# MicroController_AHRS.net
KiCad netlist of a schematic drawn in Altium Designer
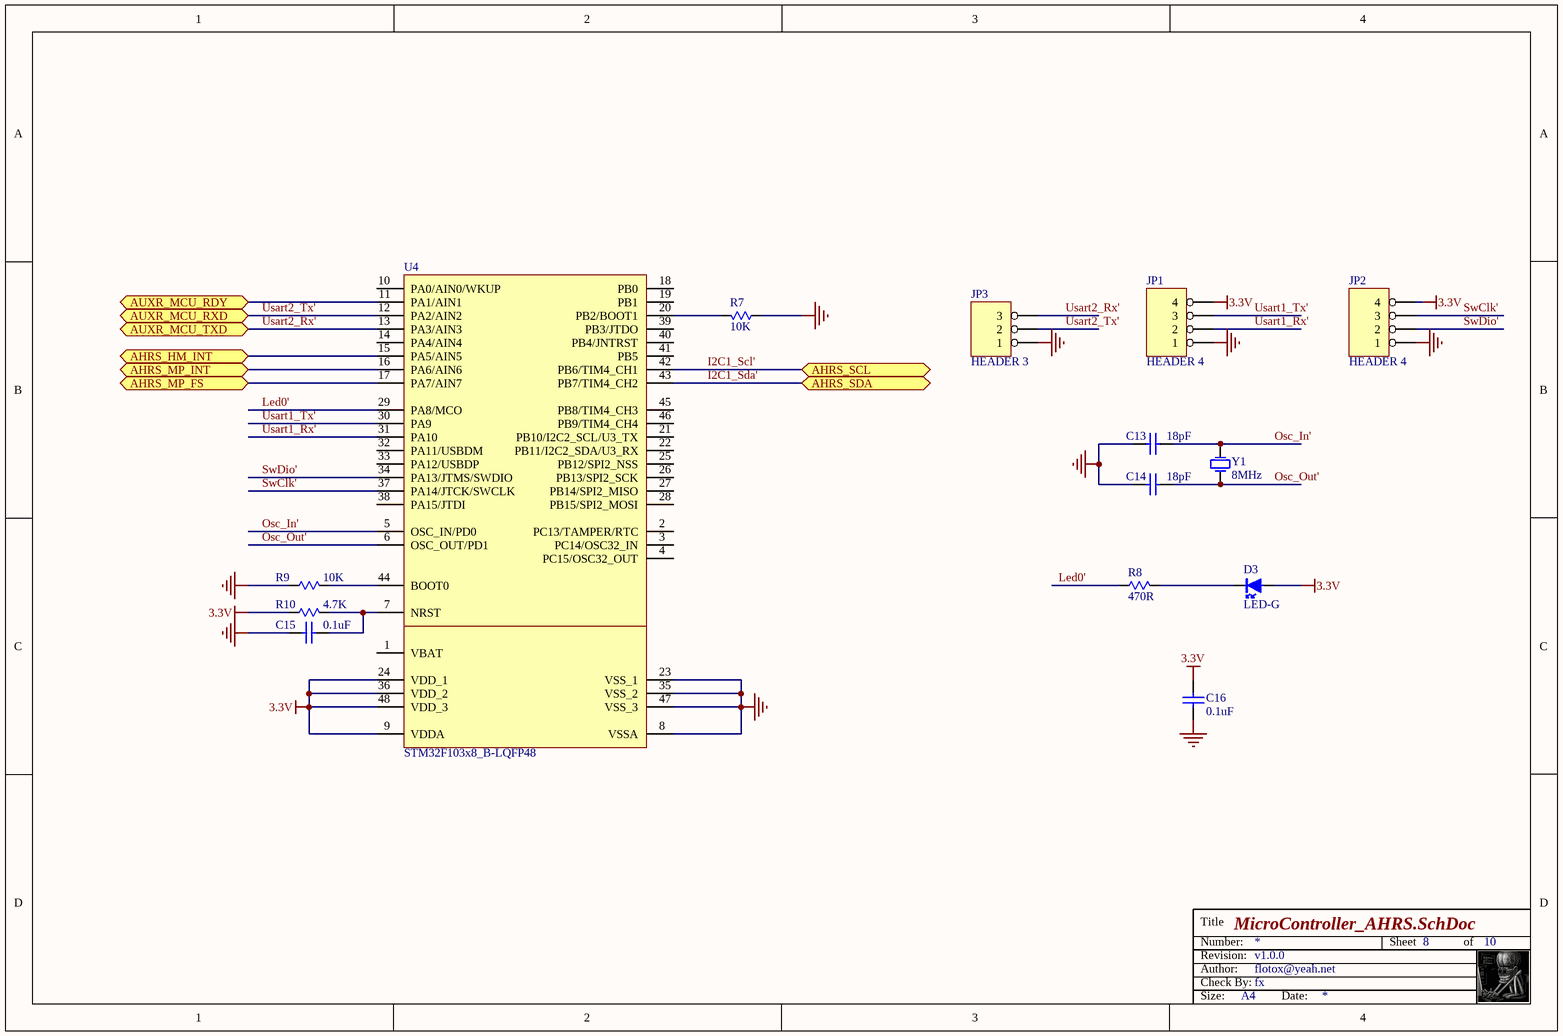
[diagram p0: MicroController_AHRS.SchDoc]

(export (version "E")
  (design (tool "Eeschema 10.0.6"))
  (components
    (comp (ref "C13")
      (value "18pF")
      (footprint "C0603-S")
      (description "Capacitor")
      (libsource (lib "Passive Components Class") (part "CAP"))
    )
    (comp (ref "C14")
      (value "18pF")
      (footprint "C0603-S")
      (description "Capacitor")
      (libsource (lib "Passive Components Class") (part "CAP"))
    )
    (comp (ref "C15")
      (value "0.1uF")
      (footprint "C0603-S")
      (description "Capacitor")
      (libsource (lib "Passive Components Class") (part "CAP"))
    )
    (comp (ref "C16")
      (value "0.1uF")
      (footprint "C0603-S")
      (description "Capacitor")
      (libsource (lib "Passive Components Class") (part "CAP"))
    )
    (comp (ref "D3")
      (value "LED-G")
      (footprint "LED0603")
      (description "Light Emitting Diode")
      (libsource (lib "Passive Components Class") (part "LED"))
    )
    (comp (ref "JP1")
      (value "HEADER 4")
      (footprint "SPOX-4P")
      (libsource (lib "Connector Class") (part "HEADER 4"))
    )
    (comp (ref "JP2")
      (value "HEADER 4")
      (footprint "HDR1X4")
      (libsource (lib "Connector Class") (part "HEADER 4"))
    )
    (comp (ref "JP3")
      (value "HEADER 3")
      (footprint "HDR1X3")
      (libsource (lib "Connector Class") (part "HEADER 3"))
    )
    (comp (ref "R7")
      (value "10K")
      (footprint "R0603-S")
      (description "Resistor")
      (libsource (lib "Passive Components Class") (part "RES"))
    )
    (comp (ref "R8")
      (value "470R")
      (footprint "R0603-S")
      (description "Resistor")
      (libsource (lib "Passive Components Class") (part "RES"))
    )
    (comp (ref "R9")
      (value "10K")
      (footprint "R0603-S")
      (description "Resistor")
      (libsource (lib "Passive Components Class") (part "RES"))
    )
    (comp (ref "R10")
      (value "4.7K")
      (footprint "R0603-S")
      (description "Resistor")
      (libsource (lib "Passive Components Class") (part "RES"))
    )
    (comp (ref "U4")
      (value "STM32F103x8_B-LQFP48")
      (footprint "LQFP7x7-48")
      (libsource (lib "Microcontrollers Class") (part "STM32F103x8_B-LQFP48"))
    )
    (comp (ref "Y1")
      (value "8MHz")
      (footprint "XTAL-49SMD")
      (description "Crystals")
      (libsource (lib "Passive Components Class") (part "XTAL-CRYSTALS"))
    )
  )
  (nets
    (net (code "1") (name "/AHRS_HM_INT") (class "Default")
      (node (ref "U4") (pin "15") (pinfunction "PA5/AIN5_15") (pintype "passive"))
    )
    (net (code "2") (name "/AHRS_MP_FS") (class "Default")
      (node (ref "U4") (pin "17") (pinfunction "PA7/AIN7_17") (pintype "passive"))
    )
    (net (code "3") (name "/AHRS_MP_INT") (class "Default")
      (node (ref "U4") (pin "16") (pinfunction "PA6/AIN6_16") (pintype "passive"))
    )
    (net (code "4") (name "/AUXR_MCU_RDY") (class "Default")
      (node (ref "U4") (pin "11") (pinfunction "PA1/AIN1_11") (pintype "passive"))
    )
    (net (code "5") (name "/I2C1_Scl'") (class "Default")
      (node (ref "U4") (pin "42") (pinfunction "PB6/TIM4_CH1_42") (pintype "passive"))
    )
    (net (code "6") (name "/I2C1_Sda'") (class "Default")
      (node (ref "U4") (pin "43") (pinfunction "PB7/TIM4_CH2_43") (pintype "passive"))
    )
    (net (code "7") (name "/Led0'") (class "Default")
      (node (ref "R8") (pin "2") (pinfunction "2_2") (pintype "passive"))
      (node (ref "U4") (pin "29") (pinfunction "PA8/MCO_29") (pintype "passive"))
    )
    (net (code "8") (name "/Osc_In'") (class "Default")
      (node (ref "C13") (pin "1") (pinfunction "1_1") (pintype "passive"))
      (node (ref "U4") (pin "5") (pinfunction "OSC_IN/PD0_5") (pintype "passive"))
      (node (ref "Y1") (pin "1") (pinfunction "OSC1_1") (pintype "passive"))
    )
    (net (code "9") (name "/Osc_Out'") (class "Default")
      (node (ref "C14") (pin "1") (pinfunction "1_1") (pintype "passive"))
      (node (ref "U4") (pin "6") (pinfunction "OSC_OUT/PD1_6") (pintype "passive"))
      (node (ref "Y1") (pin "2") (pinfunction "OSC2_2") (pintype "passive"))
    )
    (net (code "10") (name "/SwClk'") (class "Default")
      (node (ref "JP2") (pin "3") (pinfunction "3_3") (pintype "passive"))
      (node (ref "U4") (pin "37") (pinfunction "PA14/JTCK/SWCLK_37") (pintype "passive"))
    )
    (net (code "11") (name "/SwDio'") (class "Default")
      (node (ref "JP2") (pin "2") (pinfunction "2_2") (pintype "passive"))
      (node (ref "U4") (pin "34") (pinfunction "PA13/JTMS/SWDIO_34") (pintype "passive"))
    )
    (net (code "12") (name "/Usart1_Rx'") (class "Default")
      (node (ref "JP1") (pin "2") (pinfunction "2_2") (pintype "passive"))
      (node (ref "U4") (pin "31") (pinfunction "PA10_31") (pintype "passive"))
    )
    (net (code "13") (name "/Usart1_Tx'") (class "Default")
      (node (ref "JP1") (pin "3") (pinfunction "3_3") (pintype "passive"))
      (node (ref "U4") (pin "30") (pinfunction "PA9_30") (pintype "passive"))
    )
    (net (code "14") (name "/Usart2_Rx'") (class "Default")
      (node (ref "JP3") (pin "3") (pinfunction "3_3") (pintype "passive"))
      (node (ref "U4") (pin "13") (pinfunction "PA3/AIN3_13") (pintype "passive"))
    )
    (net (code "15") (name "/Usart2_Tx'") (class "Default")
      (node (ref "JP3") (pin "2") (pinfunction "2_2") (pintype "passive"))
      (node (ref "U4") (pin "12") (pinfunction "PA2/AIN2_12") (pintype "passive"))
    )
    (net (code "16") (name "3.3V") (class "Default")
      (node (ref "C16") (pin "2") (pinfunction "2_2") (pintype "passive"))
      (node (ref "D3") (pin "1") (pinfunction "A_1") (pintype "passive"))
      (node (ref "JP1") (pin "4") (pinfunction "4_4") (pintype "passive"))
      (node (ref "JP2") (pin "4") (pinfunction "4_4") (pintype "passive"))
      (node (ref "R10") (pin "2") (pinfunction "2_2") (pintype "passive"))
      (node (ref "U4") (pin "24") (pinfunction "VDD_1_24") (pintype "passive"))
      (node (ref "U4") (pin "36") (pinfunction "VDD_2_36") (pintype "passive"))
      (node (ref "U4") (pin "48") (pinfunction "VDD_3_48") (pintype "passive"))
      (node (ref "U4") (pin "9") (pinfunction "VDDA_9") (pintype "passive"))
    )
    (net (code "17") (name "GND") (class "Default")
      (node (ref "C13") (pin "2") (pinfunction "2_2") (pintype "passive"))
      (node (ref "C14") (pin "2") (pinfunction "2_2") (pintype "passive"))
      (node (ref "C15") (pin "2") (pinfunction "2_2") (pintype "passive"))
      (node (ref "C16") (pin "1") (pinfunction "1_1") (pintype "passive"))
      (node (ref "JP1") (pin "1") (pinfunction "1_1") (pintype "passive"))
      (node (ref "JP2") (pin "1") (pinfunction "1_1") (pintype "passive"))
      (node (ref "JP3") (pin "1") (pinfunction "1_1") (pintype "passive"))
      (node (ref "R7") (pin "2") (pinfunction "2_2") (pintype "passive"))
      (node (ref "R9") (pin "2") (pinfunction "2_2") (pintype "passive"))
      (node (ref "U4") (pin "23") (pinfunction "VSS_1_23") (pintype "passive"))
      (node (ref "U4") (pin "35") (pinfunction "VSS_2_35") (pintype "passive"))
      (node (ref "U4") (pin "47") (pinfunction "VSS_3_47") (pintype "passive"))
      (node (ref "U4") (pin "8") (pinfunction "VSSA_8") (pintype "passive"))
    )
    (net (code "18") (name "Net-(D3-K)") (class "Default")
      (node (ref "D3") (pin "2") (pinfunction "K_2") (pintype "passive"))
      (node (ref "R8") (pin "1") (pinfunction "1_1") (pintype "passive"))
    )
    (net (code "19") (name "Net-(U4-BOOT0)") (class "Default")
      (node (ref "R9") (pin "1") (pinfunction "1_1") (pintype "passive"))
      (node (ref "U4") (pin "44") (pinfunction "BOOT0_44") (pintype "passive"))
    )
    (net (code "20") (name "Net-(U4-NRST)") (class "Default")
      (node (ref "C15") (pin "1") (pinfunction "1_1") (pintype "passive"))
      (node (ref "R10") (pin "1") (pinfunction "1_1") (pintype "passive"))
      (node (ref "U4") (pin "7") (pinfunction "NRST_7") (pintype "passive"))
    )
    (net (code "21") (name "Net-(U4-PB2{slash}BOOT1)") (class "Default")
      (node (ref "R7") (pin "1") (pinfunction "1_1") (pintype "passive"))
      (node (ref "U4") (pin "20") (pinfunction "PB2/BOOT1_20") (pintype "passive"))
    )
    (net (code "22") (name "unconnected-(U4-PA0{slash}AIN0{slash}WKUP-Pad10)") (class "Default")
      (node (ref "U4") (pin "10") (pinfunction "PA0/AIN0/WKUP_10") (pintype "passive"))
    )
    (net (code "23") (name "unconnected-(U4-PA4{slash}AIN4-Pad14)") (class "Default")
      (node (ref "U4") (pin "14") (pinfunction "PA4/AIN4_14") (pintype "passive"))
    )
    (net (code "24") (name "unconnected-(U4-PA11{slash}USBDM-Pad32)") (class "Default")
      (node (ref "U4") (pin "32") (pinfunction "PA11/USBDM_32") (pintype "passive"))
    )
    (net (code "25") (name "unconnected-(U4-PA12{slash}USBDP-Pad33)") (class "Default")
      (node (ref "U4") (pin "33") (pinfunction "PA12/USBDP_33") (pintype "passive"))
    )
    (net (code "26") (name "unconnected-(U4-PA15{slash}JTDI-Pad38)") (class "Default")
      (node (ref "U4") (pin "38") (pinfunction "PA15/JTDI_38") (pintype "passive"))
    )
    (net (code "27") (name "unconnected-(U4-PB0-Pad18)") (class "Default")
      (node (ref "U4") (pin "18") (pinfunction "PB0_18") (pintype "passive"))
    )
    (net (code "28") (name "unconnected-(U4-PB1-Pad19)") (class "Default")
      (node (ref "U4") (pin "19") (pinfunction "PB1_19") (pintype "passive"))
    )
    (net (code "29") (name "unconnected-(U4-PB3{slash}JTDO-Pad39)") (class "Default")
      (node (ref "U4") (pin "39") (pinfunction "PB3/JTDO_39") (pintype "passive"))
    )
    (net (code "30") (name "unconnected-(U4-PB4{slash}JNTRST-Pad40)") (class "Default")
      (node (ref "U4") (pin "40") (pinfunction "PB4/JNTRST_40") (pintype "passive"))
    )
    (net (code "31") (name "unconnected-(U4-PB5-Pad41)") (class "Default")
      (node (ref "U4") (pin "41") (pinfunction "PB5_41") (pintype "passive"))
    )
    (net (code "32") (name "unconnected-(U4-PB8{slash}TIM4_CH3-Pad45)") (class "Default")
      (node (ref "U4") (pin "45") (pinfunction "PB8/TIM4_CH3_45") (pintype "passive"))
    )
    (net (code "33") (name "unconnected-(U4-PB9{slash}TIM4_CH4-Pad46)") (class "Default")
      (node (ref "U4") (pin "46") (pinfunction "PB9/TIM4_CH4_46") (pintype "passive"))
    )
    (net (code "34") (name "unconnected-(U4-PB10{slash}I2C2_SCL{slash}U3_TX-Pad21)") (class "Default")
      (node (ref "U4") (pin "21") (pinfunction "PB10/I2C2_SCL/U3_TX_21") (pintype "passive"))
    )
    (net (code "35") (name "unconnected-(U4-PB11{slash}I2C2_SDA{slash}U3_RX-Pad22)") (class "Default")
      (node (ref "U4") (pin "22") (pinfunction "PB11/I2C2_SDA/U3_RX_22") (pintype "passive"))
    )
    (net (code "36") (name "unconnected-(U4-PB12{slash}SPI2_NSS-Pad25)") (class "Default")
      (node (ref "U4") (pin "25") (pinfunction "PB12/SPI2_NSS_25") (pintype "passive"))
    )
    (net (code "37") (name "unconnected-(U4-PB13{slash}SPI2_SCK-Pad26)") (class "Default")
      (node (ref "U4") (pin "26") (pinfunction "PB13/SPI2_SCK_26") (pintype "passive"))
    )
    (net (code "38") (name "unconnected-(U4-PB14{slash}SPI2_MISO-Pad27)") (class "Default")
      (node (ref "U4") (pin "27") (pinfunction "PB14/SPI2_MISO_27") (pintype "passive"))
    )
    (net (code "39") (name "unconnected-(U4-PB15{slash}SPI2_MOSI-Pad28)") (class "Default")
      (node (ref "U4") (pin "28") (pinfunction "PB15/SPI2_MOSI_28") (pintype "passive"))
    )
    (net (code "40") (name "unconnected-(U4-PC13{slash}TAMPER{slash}RTC-Pad2)") (class "Default")
      (node (ref "U4") (pin "2") (pinfunction "PC13/TAMPER/RTC_2") (pintype "passive"))
    )
    (net (code "41") (name "unconnected-(U4-PC14{slash}OSC32_IN-Pad3)") (class "Default")
      (node (ref "U4") (pin "3") (pinfunction "PC14/OSC32_IN_3") (pintype "passive"))
    )
    (net (code "42") (name "unconnected-(U4-PC15{slash}OSC32_OUT-Pad4)") (class "Default")
      (node (ref "U4") (pin "4") (pinfunction "PC15/OSC32_OUT_4") (pintype "passive"))
    )
    (net (code "43") (name "unconnected-(U4-VBAT-Pad1)") (class "Default")
      (node (ref "U4") (pin "1") (pinfunction "VBAT_1") (pintype "passive"))
    )
  )
)
